# Controller_Board_Interface.net
KiCad netlist of a schematic drawn in Altium Designer
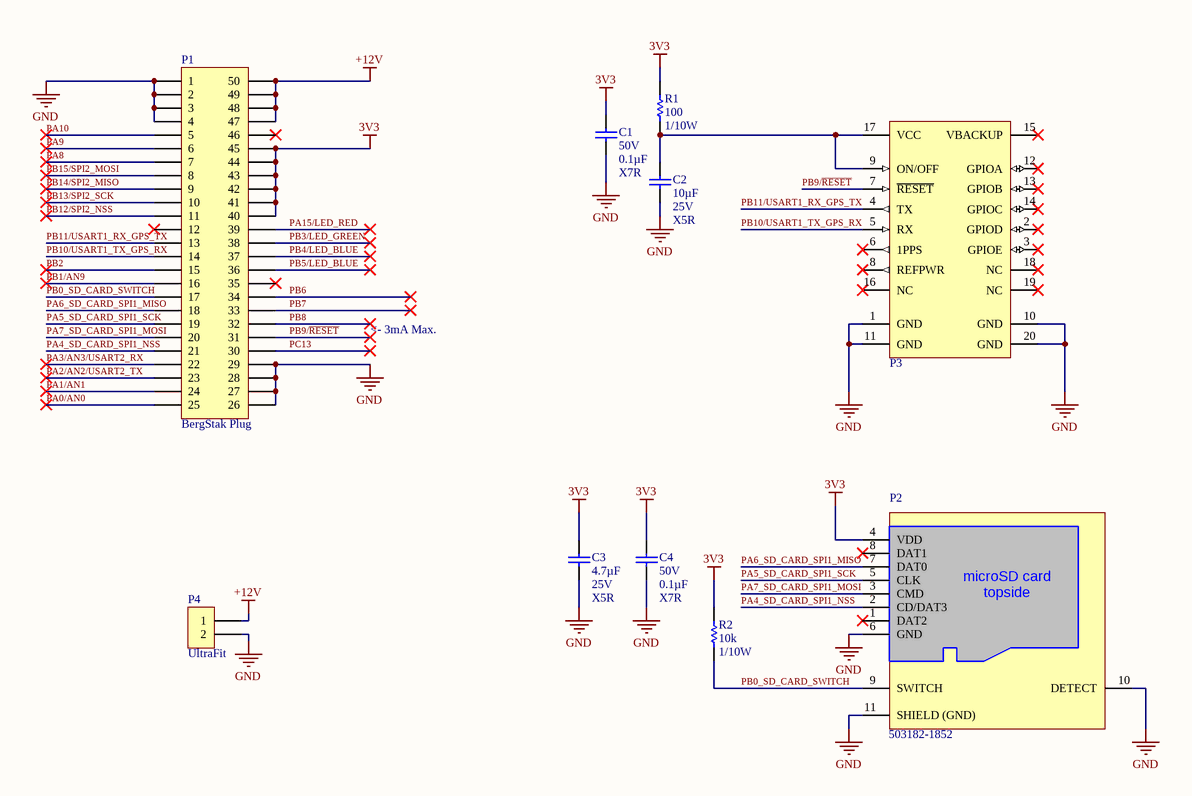
[diagram p0: Controller_Board_Interface.SchDoc]

(export (version "E")
  (design (tool "Eeschema 10.0.6"))
  (components
    (comp (ref "C1")
      (value "CAP CER 0.1UF 50V 10% X7R 0603")
      (footprint "CAP, 0603")
      (description "0.10µF ±10% 50V Ceramic Capacitor X7R 0603 (1608 Metric)")
      (fields
        (field (name "VOLTAGE") "50V")
        (field (name "TOLERANCE") "±10%")
        (field (name "CAPACITANCE") "0.1µF")
        (field (name "TEMPERATURE COEFFICIENT") "X7R")
      )
      (libsource (lib "Schematic Diagrams") (part "CAP CER 0.1UF 50V 10% X7R 0603"))
    )
    (comp (ref "C2")
      (value "CAP CER 10uF 25V 20% X5R 0603")
      (footprint "CAP, 0603")
      (description "10µF ±20% 25V Ceramic Capacitor X5R 0603 (1608 Metric)")
      (fields
        (field (name "TOLERANCE") "±20%")
        (field (name "CAPACITANCE") "10µF")
        (field (name "VOLTAGE") "25V")
        (field (name "TEMPERATURE COEFFICIENT") "X5R")
      )
      (libsource (lib "Schematic Diagrams") (part "CAP CER 10uF 25V 20% X5R 0603"))
    )
    (comp (ref "C3")
      (value "CAP CER 4.7UF 25V 10% X5R 0603")
      (footprint "CAP, 0603")
      (description "4.7µF ±10% 25V Ceramic Capacitor X5R 0603 (1608 Metric)")
      (fields
        (field (name "TOLERANCE") "±10%")
        (field (name "CAPACITANCE") "4.7µF")
        (field (name "VOLTAGE") "25V")
        (field (name "TEMPERATURE COEFFICIENT") "X5R")
      )
      (libsource (lib "altium-import") (part "root_0_CAP CER 4.7UF 25V 10% X5R 0603_"))
    )
    (comp (ref "C4")
      (value "CAP CER 0.1UF 50V 10% X7R 0603")
      (footprint "CAP, 0603")
      (description "0.10µF ±10% 50V Ceramic Capacitor X7R 0603 (1608 Metric)")
      (fields
        (field (name "VOLTAGE") "50V")
        (field (name "TOLERANCE") "±10%")
        (field (name "CAPACITANCE") "0.1µF")
        (field (name "TEMPERATURE COEFFICIENT") "X7R")
      )
      (libsource (lib "Schematic Diagrams") (part "CAP CER 0.1UF 50V 10% X7R 0603"))
    )
    (comp (ref "P1")
      (value "CONN 50POS Bergstak Plug 0.02\"")
      (footprint "CONN, Bergstak 50 Pos Plug")
      (description "50 Position Connector Plug, Outer Shroud Contacts Surface Mount Gold")
      (fields (field (name "SERIES") "BergStak Plug"))
      (libsource (lib "Schematic Diagrams") (part "CONN 50POS Bergstak Plug 0.02{dblquote}"))
    )
    (comp (ref "P2")
      (value "CONN MICRO-SD ULTRA-LOW 8CKT")
      (footprint "CONN MICRO-SD HOLDER MOLEX 503182-1852")
      (description "9 (8 + 1) Position Card Connector microSD™ Surface Mount, Right Angle Gold")
      (fields (field (name "MANUFACTURER") "Molex") (field (name "MANUFACTURER PART NUMBER") "503182-1852"))
      (libsource (lib "altium-import") (part "root_0_CONN MICRO-SD ULTRA-LOW 8CKT_"))
    )
    (comp (ref "P3")
      (value "EVAL GPS EVM-GPS-F4")
      (footprint "EVM-GPS-F4")
      (description "BOARD EVAL FOR RXM-GPS-F4")
      (libsource (lib "Schematic Diagrams") (part "EVAL GPS EVM-GPS-F4"))
    )
    (comp (ref "P4")
      (value "CONN 2POS ULTRA-FIT 0.138\"")
      (footprint "CONN, 2POS ULTRA-FIT")
      (description "2 Positions Header, Shrouded Connector 0.138\" (3.50mm) Through Hole Gold")
      (fields (field (name "VOLTAGE") "400V") (field (name "SERIES") "UltraFit"))
      (libsource (lib "Schematic Diagrams") (part "CONN 2POS ULTRA-FIT 0.138{dblquote}"))
    )
    (comp (ref "R1")
      (value "RES 100 OHM 1% 1/10W 0603")
      (footprint "RES, 0603")
      (description "100 Ohm ±1% 0.1W, 1/10W Chip Resistor 0603 (1608 Metric) Moisture Resistant Thick Film")
      (fields
        (field (name "TOLERANCE") "±1%")
        (field (name "RESISTANCE") "100")
        (field (name "POWER") "1/10W")
      )
      (libsource (lib "Schematic Diagrams") (part "RES 100 OHM 1% 1/10W 0603"))
    )
    (comp (ref "R2")
      (value "RES 10K OHM 1% 1/10W 0603")
      (footprint "RES, 0603")
      (description "RES SMD 10K OHM 1% 1/10W 0603")
      (fields
        (field (name "TOLERANCE") "±1%")
        (field (name "RESISTANCE") "10k")
        (field (name "POWER") "1/10W")
      )
      (libsource (lib "altium-import") (part "root_2_RES 10K OHM 1% 1/10W 0603_"))
    )
  )
  (nets
    (net (code "1") (name "+12V") (class "Default")
      (node (ref "P1") (pin "47") (pinfunction "47_47") (pintype "passive"))
      (node (ref "P1") (pin "48") (pinfunction "48_48") (pintype "passive"))
      (node (ref "P1") (pin "49") (pinfunction "49_49") (pintype "passive"))
      (node (ref "P1") (pin "50") (pinfunction "50_50") (pintype "passive"))
      (node (ref "P4") (pin "1") (pinfunction "1_1") (pintype "passive"))
    )
    (net (code "2") (name "/PA0{slash}AN0") (class "Default")
      (node (ref "P1") (pin "25") (pinfunction "25_25") (pintype "passive+no_connect"))
    )
    (net (code "3") (name "/PA1{slash}AN1") (class "Default")
      (node (ref "P1") (pin "24") (pinfunction "24_24") (pintype "passive+no_connect"))
    )
    (net (code "4") (name "/PA2{slash}AN2{slash}USART2_TX") (class "Default")
      (node (ref "P1") (pin "23") (pinfunction "23_23") (pintype "passive+no_connect"))
    )
    (net (code "5") (name "/PA3{slash}AN3{slash}USART2_RX") (class "Default")
      (node (ref "P1") (pin "22") (pinfunction "22_22") (pintype "passive+no_connect"))
    )
    (net (code "6") (name "/PA4_SD_CARD_SPI1_NSS") (class "Default")
      (node (ref "P1") (pin "21") (pinfunction "21_21") (pintype "passive"))
      (node (ref "P2") (pin "2") (pinfunction "CD/DAT3_2") (pintype "passive"))
    )
    (net (code "7") (name "/PA5_SD_CARD_SPI1_SCK") (class "Default")
      (node (ref "P1") (pin "19") (pinfunction "19_19") (pintype "passive"))
      (node (ref "P2") (pin "5") (pinfunction "CLK_5") (pintype "passive"))
    )
    (net (code "8") (name "/PA6_SD_CARD_SPI1_MISO") (class "Default")
      (node (ref "P1") (pin "18") (pinfunction "18_18") (pintype "passive"))
      (node (ref "P2") (pin "7") (pinfunction "DAT0_7") (pintype "passive"))
    )
    (net (code "9") (name "/PA7_SD_CARD_SPI1_MOSI") (class "Default")
      (node (ref "P1") (pin "20") (pinfunction "20_20") (pintype "passive"))
      (node (ref "P2") (pin "3") (pinfunction "CMD_3") (pintype "passive"))
    )
    (net (code "10") (name "/PA8") (class "Default")
      (node (ref "P1") (pin "7") (pinfunction "7_7") (pintype "passive+no_connect"))
    )
    (net (code "11") (name "/PA9") (class "Default")
      (node (ref "P1") (pin "6") (pinfunction "6_6") (pintype "passive+no_connect"))
    )
    (net (code "12") (name "/PA10") (class "Default")
      (node (ref "P1") (pin "5") (pinfunction "5_5") (pintype "passive+no_connect"))
    )
    (net (code "13") (name "/PA15{slash}LED_RED") (class "Default")
      (node (ref "P1") (pin "39") (pinfunction "39_39") (pintype "passive+no_connect"))
    )
    (net (code "14") (name "/PB0_SD_CARD_SWITCH") (class "Default")
      (node (ref "P1") (pin "17") (pinfunction "17_17") (pintype "passive"))
      (node (ref "P2") (pin "9") (pinfunction "SWITCH_9") (pintype "passive"))
      (node (ref "R2") (pin "1") (pinfunction "1_1") (pintype "passive"))
    )
    (net (code "15") (name "/PB1{slash}AN9") (class "Default")
      (node (ref "P1") (pin "16") (pinfunction "16_16") (pintype "passive+no_connect"))
    )
    (net (code "16") (name "/PB2") (class "Default")
      (node (ref "P1") (pin "15") (pinfunction "15_15") (pintype "passive+no_connect"))
    )
    (net (code "17") (name "/PB3{slash}LED_GREEN") (class "Default")
      (node (ref "P1") (pin "38") (pinfunction "38_38") (pintype "passive+no_connect"))
    )
    (net (code "18") (name "/PB4{slash}LED_BLUE") (class "Default")
      (node (ref "P1") (pin "37") (pinfunction "37_37") (pintype "passive+no_connect"))
    )
    (net (code "19") (name "/PB5{slash}LED_BLUE") (class "Default")
      (node (ref "P1") (pin "36") (pinfunction "36_36") (pintype "passive+no_connect"))
    )
    (net (code "20") (name "/PB6") (class "Default")
      (node (ref "P1") (pin "34") (pinfunction "34_34") (pintype "passive+no_connect"))
    )
    (net (code "21") (name "/PB7") (class "Default")
      (node (ref "P1") (pin "33") (pinfunction "33_33") (pintype "passive+no_connect"))
    )
    (net (code "22") (name "/PB8") (class "Default")
      (node (ref "P1") (pin "32") (pinfunction "32_32") (pintype "passive+no_connect"))
    )
    (net (code "23") (name "/PB9{slash}~{RESET}") (class "Default")
      (node (ref "P1") (pin "31") (pinfunction "31_31") (pintype "passive"))
      (node (ref "P3") (pin "7") (pinfunction "~{RESET}_7") (pintype "input"))
    )
    (net (code "24") (name "/PB10{slash}USART1_TX_GPS_RX") (class "Default")
      (node (ref "P1") (pin "14") (pinfunction "14_14") (pintype "passive"))
      (node (ref "P3") (pin "5") (pinfunction "RX_5") (pintype "input"))
    )
    (net (code "25") (name "/PB11{slash}USART1_RX_GPS_TX") (class "Default")
      (node (ref "P1") (pin "13") (pinfunction "13_13") (pintype "passive"))
      (node (ref "P3") (pin "4") (pinfunction "TX_4") (pintype "output"))
    )
    (net (code "26") (name "/PB12{slash}SPI2_NSS") (class "Default")
      (node (ref "P1") (pin "11") (pinfunction "11_11") (pintype "passive+no_connect"))
    )
    (net (code "27") (name "/PB13{slash}SPI2_SCK") (class "Default")
      (node (ref "P1") (pin "10") (pinfunction "10_10") (pintype "passive+no_connect"))
    )
    (net (code "28") (name "/PB14{slash}SPI2_MISO") (class "Default")
      (node (ref "P1") (pin "9") (pinfunction "9_9") (pintype "passive+no_connect"))
    )
    (net (code "29") (name "/PB15{slash}SPI2_MOSI") (class "Default")
      (node (ref "P1") (pin "8") (pinfunction "8_8") (pintype "passive+no_connect"))
    )
    (net (code "30") (name "/PC13") (class "Default")
      (node (ref "P1") (pin "30") (pinfunction "30_30") (pintype "passive+no_connect"))
    )
    (net (code "31") (name "3V3") (class "Default")
      (node (ref "C1") (pin "2") (pinfunction "2_2") (pintype "passive"))
      (node (ref "C3") (pin "1") (pinfunction "1_1") (pintype "passive"))
      (node (ref "C4") (pin "2") (pinfunction "2_2") (pintype "passive"))
      (node (ref "P1") (pin "40") (pinfunction "40_40") (pintype "passive"))
      (node (ref "P1") (pin "41") (pinfunction "41_41") (pintype "passive"))
      (node (ref "P1") (pin "42") (pinfunction "42_42") (pintype "passive"))
      (node (ref "P1") (pin "43") (pinfunction "43_43") (pintype "passive"))
      (node (ref "P1") (pin "44") (pinfunction "44_44") (pintype "passive"))
      (node (ref "P1") (pin "45") (pinfunction "45_45") (pintype "passive"))
      (node (ref "P2") (pin "4") (pinfunction "VDD_4") (pintype "passive"))
      (node (ref "R1") (pin "1") (pinfunction "1_1") (pintype "passive"))
      (node (ref "R2") (pin "2") (pinfunction "2_2") (pintype "passive"))
    )
    (net (code "32") (name "GND") (class "Default")
      (node (ref "C1") (pin "1") (pinfunction "1_1") (pintype "passive"))
      (node (ref "C2") (pin "2") (pinfunction "2_2") (pintype "passive"))
      (node (ref "C3") (pin "2") (pinfunction "2_2") (pintype "passive"))
      (node (ref "C4") (pin "1") (pinfunction "1_1") (pintype "passive"))
      (node (ref "P1") (pin "1") (pinfunction "1_1") (pintype "passive"))
      (node (ref "P1") (pin "2") (pinfunction "2_2") (pintype "passive"))
      (node (ref "P1") (pin "26") (pinfunction "26_26") (pintype "passive"))
      (node (ref "P1") (pin "27") (pinfunction "27_27") (pintype "passive"))
      (node (ref "P1") (pin "28") (pinfunction "28_28") (pintype "passive"))
      (node (ref "P1") (pin "29") (pinfunction "29_29") (pintype "passive"))
      (node (ref "P1") (pin "3") (pinfunction "3_3") (pintype "passive"))
      (node (ref "P1") (pin "4") (pinfunction "4_4") (pintype "passive"))
      (node (ref "P2") (pin "10") (pinfunction "DETECT_10") (pintype "passive"))
      (node (ref "P2") (pin "11") (pinfunction "SHIELD_(GND)_11") (pintype "passive"))
      (node (ref "P2") (pin "6") (pinfunction "GND_6") (pintype "passive"))
      (node (ref "P3") (pin "1") (pinfunction "GND_1") (pintype "power_in"))
      (node (ref "P3") (pin "10") (pinfunction "GND_10") (pintype "power_in"))
      (node (ref "P3") (pin "11") (pinfunction "GND_11") (pintype "power_in"))
      (node (ref "P3") (pin "20") (pinfunction "GND_20") (pintype "power_in"))
      (node (ref "P4") (pin "2") (pinfunction "2_2") (pintype "passive"))
    )
    (net (code "33") (name "Net-(P3-ON{slash}OFF)") (class "Default")
      (node (ref "C2") (pin "1") (pinfunction "1_1") (pintype "passive"))
      (node (ref "P3") (pin "17") (pinfunction "VCC_17") (pintype "power_in"))
      (node (ref "P3") (pin "9") (pinfunction "ON/OFF_9") (pintype "input"))
      (node (ref "R1") (pin "2") (pinfunction "2_2") (pintype "passive"))
    )
    (net (code "34") (name "unconnected-(P1-Pad12)") (class "Default")
      (node (ref "P1") (pin "12") (pinfunction "12_12") (pintype "passive+no_connect"))
    )
    (net (code "35") (name "unconnected-(P1-Pad35)") (class "Default")
      (node (ref "P1") (pin "35") (pinfunction "35_35") (pintype "passive+no_connect"))
    )
    (net (code "36") (name "unconnected-(P1-Pad46)") (class "Default")
      (node (ref "P1") (pin "46") (pinfunction "46_46") (pintype "passive+no_connect"))
    )
    (net (code "37") (name "unconnected-(P2-DAT1-Pad8)") (class "Default")
      (node (ref "P2") (pin "8") (pinfunction "DAT1_8") (pintype "passive+no_connect"))
    )
    (net (code "38") (name "unconnected-(P2-DAT2-Pad1)") (class "Default")
      (node (ref "P2") (pin "1") (pinfunction "DAT2_1") (pintype "passive+no_connect"))
    )
    (net (code "39") (name "unconnected-(P3-1PPS-Pad6)") (class "Default")
      (node (ref "P3") (pin "6") (pinfunction "1PPS_6") (pintype "output+no_connect"))
    )
    (net (code "40") (name "unconnected-(P3-GPIOA-Pad12)") (class "Default")
      (node (ref "P3") (pin "12") (pinfunction "GPIOA_12") (pintype "bidirectional+no_connect"))
    )
    (net (code "41") (name "unconnected-(P3-GPIOB-Pad13)") (class "Default")
      (node (ref "P3") (pin "13") (pinfunction "GPIOB_13") (pintype "bidirectional+no_connect"))
    )
    (net (code "42") (name "unconnected-(P3-GPIOC-Pad14)") (class "Default")
      (node (ref "P3") (pin "14") (pinfunction "GPIOC_14") (pintype "bidirectional+no_connect"))
    )
    (net (code "43") (name "unconnected-(P3-GPIOD-Pad2)") (class "Default")
      (node (ref "P3") (pin "2") (pinfunction "GPIOD_2") (pintype "bidirectional+no_connect"))
    )
    (net (code "44") (name "unconnected-(P3-GPIOE-Pad3)") (class "Default")
      (node (ref "P3") (pin "3") (pinfunction "GPIOE_3") (pintype "bidirectional+no_connect"))
    )
    (net (code "45") (name "unconnected-(P3-NC-Pad16)") (class "Default")
      (node (ref "P3") (pin "16") (pinfunction "NC_16") (pintype "passive+no_connect"))
    )
    (net (code "46") (name "unconnected-(P3-NC-Pad18)") (class "Default")
      (node (ref "P3") (pin "18") (pinfunction "NC_18") (pintype "passive+no_connect"))
    )
    (net (code "47") (name "unconnected-(P3-NC-Pad19)") (class "Default")
      (node (ref "P3") (pin "19") (pinfunction "NC_19") (pintype "passive+no_connect"))
    )
    (net (code "48") (name "unconnected-(P3-REFPWR-Pad8)") (class "Default")
      (node (ref "P3") (pin "8") (pinfunction "REFPWR_8") (pintype "output+no_connect"))
    )
    (net (code "49") (name "unconnected-(P3-VBACKUP-Pad15)") (class "Default")
      (node (ref "P3") (pin "15") (pinfunction "VBACKUP_15") (pintype "power_in+no_connect"))
    )
  )
)
